# Communications.net
KiCad netlist of a schematic drawn in Altium Designer
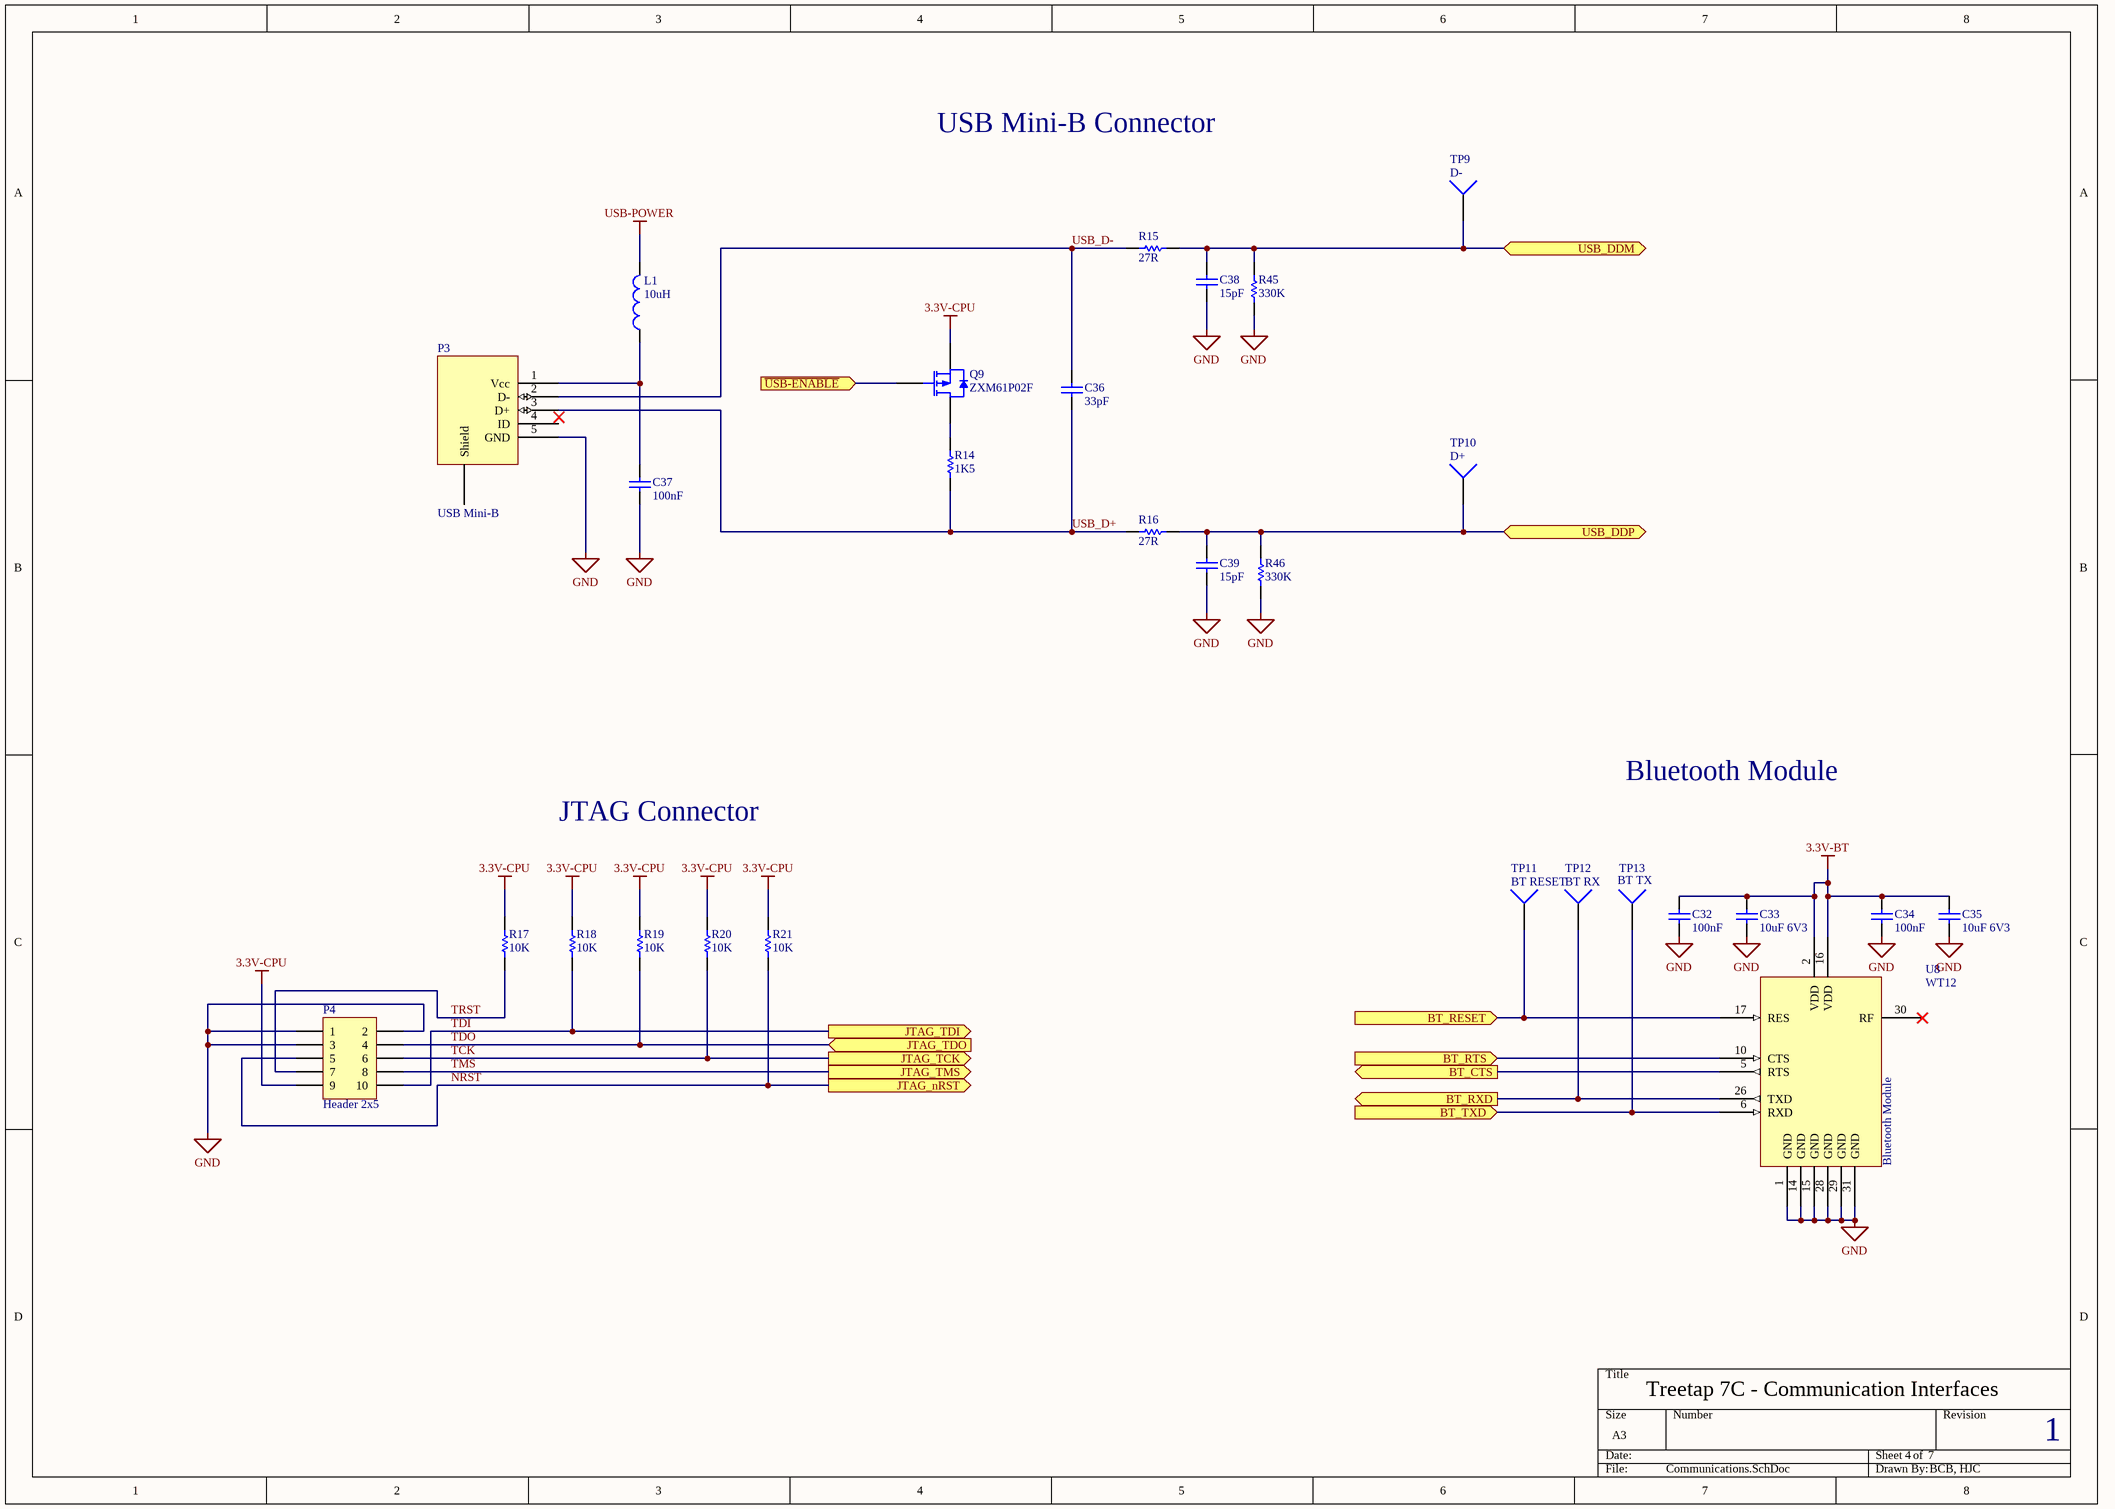
[diagram p0: Communications.SchDoc]

(export (version "E")
  (design (tool "Eeschema 10.0.6"))
  (components
    (comp (ref "C32")
      (value "100nF")
      (footprint "CC0603")
      (description "0603 Capacitor")
      (fields (field (name "PART NUMBER") "100nF_CC0603"))
      (libsource (lib "ECE_Component_Library_2") (part "100nF_CC0603"))
    )
    (comp (ref "C33")
      (value "10uF 6V3")
      (footprint "CC0603")
      (description "10uF 6.3V 0603 ceramic capacitor")
      (fields (field (name "MANUFACTURER") "Multicomp") (field (name "PART NUMBER") "MCCA000517"))
      (libsource (lib "TreetapParts") (part "10uF_CC0603_6V3"))
    )
    (comp (ref "C34")
      (value "100nF")
      (footprint "CC0603")
      (description "0603 Capacitor")
      (fields (field (name "PART NUMBER") "100nF_CC0603"))
      (libsource (lib "ECE_Component_Library_2") (part "100nF_CC0603"))
    )
    (comp (ref "C35")
      (value "10uF 6V3")
      (footprint "CC0603")
      (description "10uF 6.3V 0603 ceramic capacitor")
      (fields (field (name "MANUFACTURER") "Multicomp") (field (name "PART NUMBER") "MCCA000517"))
      (libsource (lib "TreetapParts") (part "10uF_CC0603_6V3"))
    )
    (comp (ref "C36")
      (value "33pF")
      (footprint "CC0603")
      (description "0603 Capacitor")
      (fields (field (name "PART NUMBER") "33pF_CC0603"))
      (libsource (lib "ECE_Component_Library_2") (part "33pF_CC0603"))
    )
    (comp (ref "C37")
      (value "100nF")
      (footprint "CC0603")
      (description "0603 Capacitor")
      (fields (field (name "PART NUMBER") "100nF_CC0603"))
      (libsource (lib "ECE_Component_Library_2") (part "100nF_CC0603"))
    )
    (comp (ref "C38")
      (value "15pF")
      (footprint "CC0603")
      (description "0603 Capacitor")
      (fields (field (name "PART NUMBER") "15pF_CC0603"))
      (libsource (lib "ECE_Component_Library_2") (part "15pF_CC0603"))
    )
    (comp (ref "C39")
      (value "15pF")
      (footprint "CC0603")
      (description "0603 Capacitor")
      (fields (field (name "PART NUMBER") "15pF_CC0603"))
      (libsource (lib "ECE_Component_Library_2") (part "15pF_CC0603"))
    )
    (comp (ref "L1")
      (value "10uH")
      (footprint "0805")
      (description "10uH ferrite bead")
      (fields (field (name "MANUFACTURER") "Tyco Electronics") (field (name "PART NUMBER") "BMB2A0300AN1"))
      (libsource (lib "TreetapParts") (part "10uH_ferrite"))
    )
    (comp (ref "P3")
      (value "USB Mini-B")
      (footprint "USBminiB")
      (description "USB mini B-type connector, surface mount with shield")
      (fields (field (name "MANUFACTURER") "Molex") (field (name "PART NUMBER") "678038020"))
      (libsource (lib "TreetapParts") (part "USBminiB"))
    )
    (comp (ref "P4")
      (value "Header 2x5")
      (footprint "HEADER 2x5")
      (description "SMD Header, 2x5, boxed")
      (fields (field (name "MANUFACTURER") "3M") (field (name "PART NUMBER") "N2510-6V0C-RB-WD"))
      (libsource (lib "TreetapParts") (part "HEADER 2x5"))
    )
    (comp (ref "Q9")
      (value "ZXM61P02F")
      (footprint "SOT-23")
      (description "20V P-channel enhancement mode MOSFET")
      (fields (field (name "MANUFACTURER") "Zetex"))
      (libsource (lib "TreetapParts") (part "ZXM61P02F"))
    )
    (comp (ref "R14")
      (value "1K5")
      (footprint "R0603")
      (description "0603 Resistor")
      (fields (field (name "PART NUMBER") "1K5_R0603"))
      (libsource (lib "ECE_Component_Library_2") (part "1K5_R0603"))
    )
    (comp (ref "R15")
      (value "27R")
      (footprint "R0603")
      (description "0603 Resistor")
      (fields (field (name "PART NUMBER") "27R_R0603"))
      (libsource (lib "ECE_Component_Library_2") (part "27R_R0603"))
    )
    (comp (ref "R16")
      (value "27R")
      (footprint "R0603")
      (description "0603 Resistor")
      (fields (field (name "PART NUMBER") "27R_R0603"))
      (libsource (lib "ECE_Component_Library_2") (part "27R_R0603"))
    )
    (comp (ref "R17")
      (value "10K")
      (footprint "R0603")
      (description "0603 Resistor")
      (fields (field (name "PART NUMBER") "10K_R0603"))
      (libsource (lib "ECE_Component_Library_2") (part "10K_R0603"))
    )
    (comp (ref "R18")
      (value "10K")
      (footprint "R0603")
      (description "0603 Resistor")
      (fields (field (name "PART NUMBER") "10K_R0603"))
      (libsource (lib "ECE_Component_Library_2") (part "10K_R0603"))
    )
    (comp (ref "R19")
      (value "10K")
      (footprint "R0603")
      (description "0603 Resistor")
      (fields (field (name "PART NUMBER") "10K_R0603"))
      (libsource (lib "ECE_Component_Library_2") (part "10K_R0603"))
    )
    (comp (ref "R20")
      (value "10K")
      (footprint "R0603")
      (description "0603 Resistor")
      (fields (field (name "PART NUMBER") "10K_R0603"))
      (libsource (lib "ECE_Component_Library_2") (part "10K_R0603"))
    )
    (comp (ref "R21")
      (value "10K")
      (footprint "R0603")
      (description "0603 Resistor")
      (fields (field (name "PART NUMBER") "10K_R0603"))
      (libsource (lib "ECE_Component_Library_2") (part "10K_R0603"))
    )
    (comp (ref "R45")
      (value "330K")
      (footprint "R0603")
      (description "0603 Resistor")
      (fields (field (name "PART NUMBER") "330K_R0603"))
      (libsource (lib "ECE_Component_Library_2") (part "330K_R0603"))
    )
    (comp (ref "R46")
      (value "330K")
      (footprint "R0603")
      (description "0603 Resistor")
      (fields (field (name "PART NUMBER") "330K_R0603"))
      (libsource (lib "ECE_Component_Library_2") (part "330K_R0603"))
    )
    (comp (ref "TP9")
      (value "D-")
      (footprint "SMTP_1")
      (description "Test point hook (surface mount)")
      (fields (field (name "MANUFACTURER") "Harwin") (field (name "PART NUMBER") "S1751-46"))
      (libsource (lib "TreetapParts") (part "SMTestPoint"))
    )
    (comp (ref "TP10")
      (value "D+")
      (footprint "SMTP_1")
      (description "Test point hook (surface mount)")
      (fields (field (name "MANUFACTURER") "Harwin") (field (name "PART NUMBER") "S1751-46"))
      (libsource (lib "TreetapParts") (part "SMTestPoint"))
    )
    (comp (ref "TP11")
      (value "BT RESET")
      (footprint "SMTP_1")
      (description "Test point hook (surface mount)")
      (fields (field (name "MANUFACTURER") "Harwin") (field (name "PART NUMBER") "S1751-46"))
      (libsource (lib "TreetapParts") (part "SMTestPoint"))
    )
    (comp (ref "TP12")
      (value "BT RX")
      (footprint "SMTP_1")
      (description "Test point hook (surface mount)")
      (fields (field (name "MANUFACTURER") "Harwin") (field (name "PART NUMBER") "S1751-46"))
      (libsource (lib "TreetapParts") (part "SMTestPoint"))
    )
    (comp (ref "TP13")
      (value "BT TX")
      (footprint "SMTP_1")
      (description "Test point hook (surface mount)")
      (fields (field (name "MANUFACTURER") "Harwin") (field (name "PART NUMBER") "S1751-46"))
      (libsource (lib "TreetapParts") (part "SMTestPoint"))
    )
    (comp (ref "U8")
      (value "WT12")
      (footprint "WT12_Bluetooth")
      (description "Bluetooth Module Block")
      (fields (field (name "MANUFACTURER") "Bluegiga") (field (name "PART NUMBER") "WT12-A-AI"))
      (libsource (lib "TreetapParts") (part "WT12_Bluetooth"))
    )
  )
  (nets
    (net (code "1") (name "/BT_CTS") (class "Default")
      (node (ref "U8") (pin "5") (pinfunction "RTS_5") (pintype "output"))
    )
    (net (code "2") (name "/BT_RESET") (class "Default")
      (node (ref "TP11") (pin "1") (pinfunction "1_1") (pintype "passive"))
      (node (ref "U8") (pin "17") (pinfunction "RES_17") (pintype "input"))
    )
    (net (code "3") (name "/BT_RTS") (class "Default")
      (node (ref "U8") (pin "10") (pinfunction "CTS_10") (pintype "input"))
    )
    (net (code "4") (name "/BT_RXD") (class "Default")
      (node (ref "TP12") (pin "1") (pinfunction "1_1") (pintype "passive"))
      (node (ref "U8") (pin "26") (pinfunction "TXD_26") (pintype "output"))
    )
    (net (code "5") (name "/BT_TXD") (class "Default")
      (node (ref "TP13") (pin "1") (pinfunction "1_1") (pintype "passive"))
      (node (ref "U8") (pin "6") (pinfunction "RXD_6") (pintype "input"))
    )
    (net (code "6") (name "/NRST") (class "Default")
      (node (ref "P4") (pin "5") (pinfunction "5_5") (pintype "passive"))
      (node (ref "R21") (pin "1") (pinfunction "1_1") (pintype "passive"))
    )
    (net (code "7") (name "/TCK") (class "Default")
      (node (ref "P4") (pin "6") (pinfunction "6_6") (pintype "passive"))
      (node (ref "R20") (pin "1") (pinfunction "1_1") (pintype "passive"))
    )
    (net (code "8") (name "/TDI") (class "Default")
      (node (ref "P4") (pin "10") (pinfunction "10_10") (pintype "passive"))
      (node (ref "R18") (pin "1") (pinfunction "1_1") (pintype "passive"))
    )
    (net (code "9") (name "/TDO") (class "Default")
      (node (ref "P4") (pin "4") (pinfunction "4_4") (pintype "passive"))
      (node (ref "R19") (pin "1") (pinfunction "1_1") (pintype "passive"))
    )
    (net (code "10") (name "/TMS") (class "Default")
      (node (ref "P4") (pin "8") (pinfunction "8_8") (pintype "passive"))
    )
    (net (code "11") (name "/TRST") (class "Default")
      (node (ref "P4") (pin "7") (pinfunction "7_7") (pintype "passive"))
      (node (ref "R17") (pin "1") (pinfunction "1_1") (pintype "passive"))
    )
    (net (code "12") (name "/USB_D+") (class "Default")
      (node (ref "C36") (pin "1") (pinfunction "1_1") (pintype "passive"))
      (node (ref "P3") (pin "3") (pinfunction "D+_3") (pintype "bidirectional"))
      (node (ref "R14") (pin "1") (pinfunction "1_1") (pintype "passive"))
      (node (ref "R16") (pin "1") (pinfunction "1_1") (pintype "passive"))
    )
    (net (code "13") (name "/USB_D-") (class "Default")
      (node (ref "C36") (pin "2") (pinfunction "2_2") (pintype "passive"))
      (node (ref "P3") (pin "2") (pinfunction "D-_2") (pintype "bidirectional"))
      (node (ref "R15") (pin "1") (pinfunction "1_1") (pintype "passive"))
    )
    (net (code "14") (name "/USB_DDM") (class "Default")
      (node (ref "C38") (pin "2") (pinfunction "2_2") (pintype "passive"))
      (node (ref "R15") (pin "2") (pinfunction "2_2") (pintype "passive"))
      (node (ref "R45") (pin "2") (pinfunction "2_2") (pintype "passive"))
      (node (ref "TP9") (pin "1") (pinfunction "1_1") (pintype "passive"))
    )
    (net (code "15") (name "/USB_DDP") (class "Default")
      (node (ref "C39") (pin "2") (pinfunction "2_2") (pintype "passive"))
      (node (ref "R16") (pin "2") (pinfunction "2_2") (pintype "passive"))
      (node (ref "R46") (pin "2") (pinfunction "2_2") (pintype "passive"))
      (node (ref "TP10") (pin "1") (pinfunction "1_1") (pintype "passive"))
    )
    (net (code "16") (name "/~{USB-ENABLE}") (class "Default")
      (node (ref "Q9") (pin "1") (pinfunction "G_1") (pintype "passive"))
    )
    (net (code "17") (name "3.3V-BT") (class "Default")
      (node (ref "C32") (pin "2") (pinfunction "2_2") (pintype "passive"))
      (node (ref "C33") (pin "2") (pinfunction "2_2") (pintype "passive"))
      (node (ref "C34") (pin "2") (pinfunction "2_2") (pintype "passive"))
      (node (ref "C35") (pin "2") (pinfunction "2_2") (pintype "passive"))
      (node (ref "U8") (pin "16") (pinfunction "VDD_16") (pintype "power_in"))
      (node (ref "U8") (pin "2") (pinfunction "VDD_2") (pintype "power_in"))
    )
    (net (code "18") (name "3.3V-CPU") (class "Default")
      (node (ref "P4") (pin "9") (pinfunction "9_9") (pintype "passive"))
      (node (ref "Q9") (pin "2") (pinfunction "S_2") (pintype "passive"))
      (node (ref "R17") (pin "2") (pinfunction "2_2") (pintype "passive"))
      (node (ref "R18") (pin "2") (pinfunction "2_2") (pintype "passive"))
      (node (ref "R19") (pin "2") (pinfunction "2_2") (pintype "passive"))
      (node (ref "R20") (pin "2") (pinfunction "2_2") (pintype "passive"))
      (node (ref "R21") (pin "2") (pinfunction "2_2") (pintype "passive"))
    )
    (net (code "19") (name "GND") (class "Default")
      (node (ref "C32") (pin "1") (pinfunction "1_1") (pintype "passive"))
      (node (ref "C33") (pin "1") (pinfunction "1_1") (pintype "passive"))
      (node (ref "C34") (pin "1") (pinfunction "1_1") (pintype "passive"))
      (node (ref "C35") (pin "1") (pinfunction "1_1") (pintype "passive"))
      (node (ref "C37") (pin "1") (pinfunction "1_1") (pintype "passive"))
      (node (ref "C38") (pin "1") (pinfunction "1_1") (pintype "passive"))
      (node (ref "C39") (pin "1") (pinfunction "1_1") (pintype "passive"))
      (node (ref "P3") (pin "5") (pinfunction "GND_5") (pintype "power_in"))
      (node (ref "P4") (pin "1") (pinfunction "1_1") (pintype "passive"))
      (node (ref "P4") (pin "2") (pinfunction "2_2") (pintype "passive"))
      (node (ref "P4") (pin "3") (pinfunction "3_3") (pintype "passive"))
      (node (ref "R45") (pin "1") (pinfunction "1_1") (pintype "passive"))
      (node (ref "R46") (pin "1") (pinfunction "1_1") (pintype "passive"))
      (node (ref "U8") (pin "1") (pinfunction "GND_1") (pintype "power_in"))
      (node (ref "U8") (pin "14") (pinfunction "GND_14") (pintype "power_in"))
      (node (ref "U8") (pin "15") (pinfunction "GND_15") (pintype "power_in"))
      (node (ref "U8") (pin "28") (pinfunction "GND_28") (pintype "power_in"))
      (node (ref "U8") (pin "29") (pinfunction "GND_29") (pintype "power_in"))
      (node (ref "U8") (pin "31") (pinfunction "GND_31") (pintype "power_in"))
    )
    (net (code "20") (name "Net-(P3-Vcc)") (class "Default")
      (node (ref "C37") (pin "2") (pinfunction "2_2") (pintype "passive"))
      (node (ref "L1") (pin "1") (pinfunction "1_1") (pintype "passive"))
      (node (ref "P3") (pin "1") (pinfunction "Vcc_1") (pintype "power_in"))
    )
    (net (code "21") (name "Net-(Q9-D)") (class "Default")
      (node (ref "Q9") (pin "3") (pinfunction "D_3") (pintype "passive"))
      (node (ref "R14") (pin "2") (pinfunction "2_2") (pintype "passive"))
    )
    (net (code "22") (name "USB-POWER") (class "Default")
      (node (ref "L1") (pin "2") (pinfunction "2_2") (pintype "passive"))
    )
    (net (code "23") (name "unconnected-(P3-ID-Pad4)") (class "Default")
      (node (ref "P3") (pin "4") (pinfunction "ID_4") (pintype "passive"))
    )
    (net (code "24") (name "unconnected-(P3-PadShield)") (class "Default")
      (node (ref "P3") (pin "Shield") (pinfunction "Shield_Shield") (pintype "passive"))
    )
    (net (code "25") (name "unconnected-(U8-RF-Pad30)") (class "Default")
      (node (ref "U8") (pin "30") (pinfunction "RF_30") (pintype "power_in+no_connect"))
    )
  )
)
